# Screens.net
KiCad netlist of a schematic drawn in Altium Designer
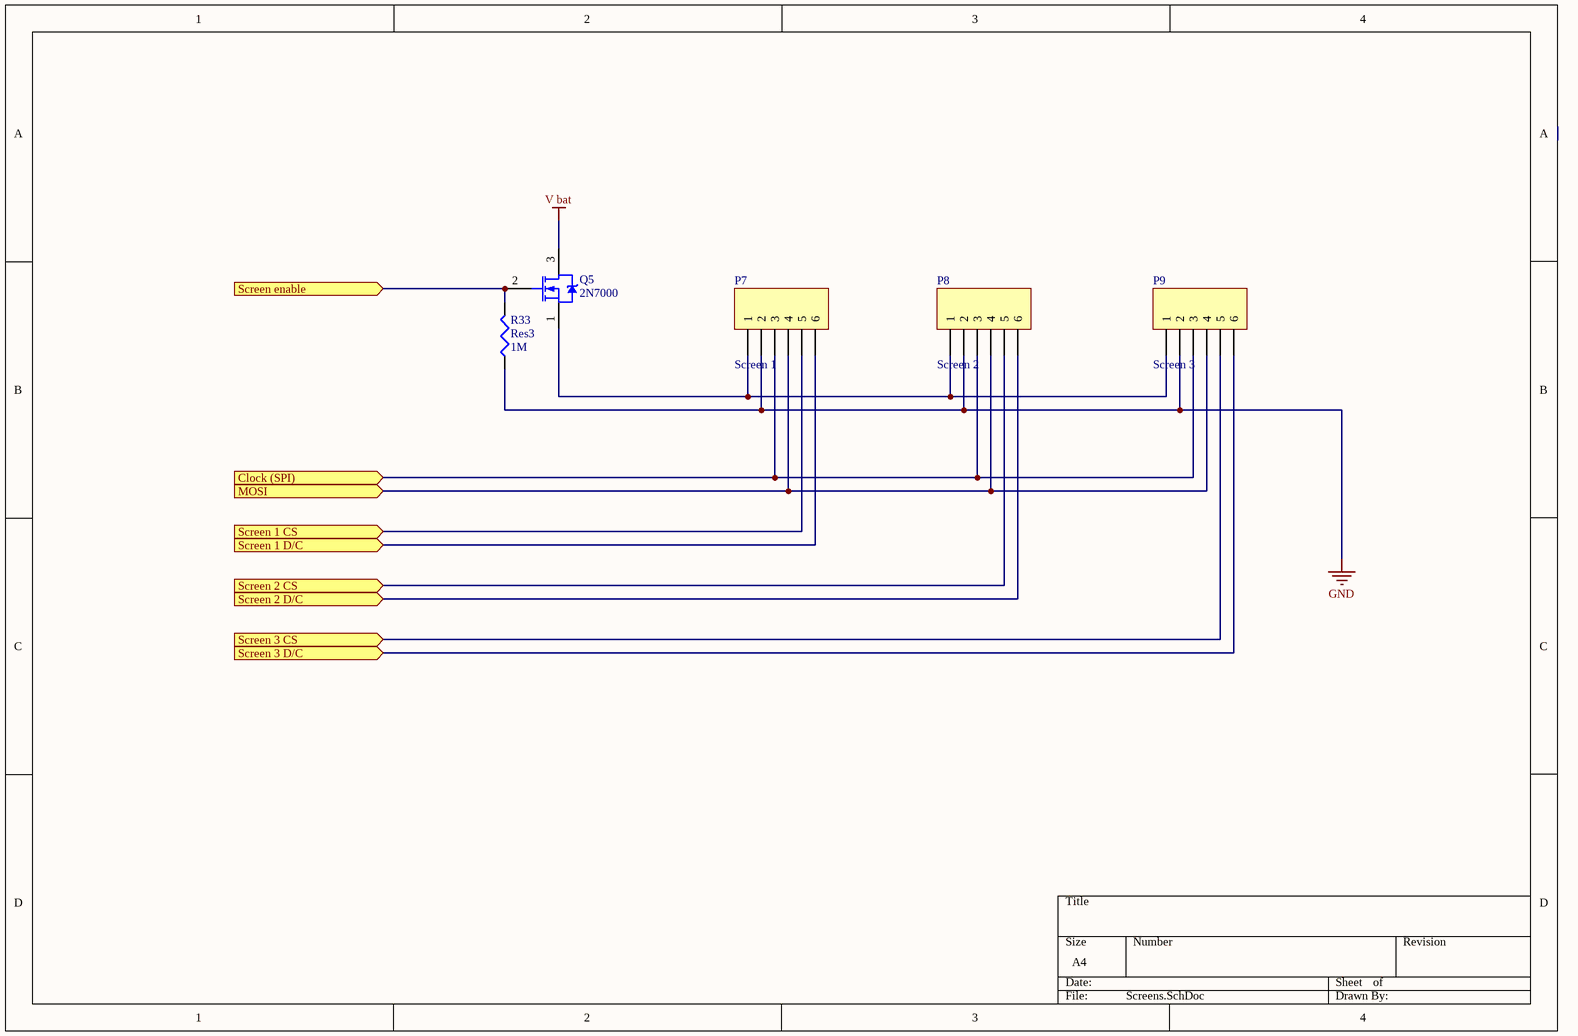
[diagram p0: Screens.SchDoc]

(export (version "E")
  (design (tool "Eeschema 10.0.6"))
  (components
    (comp (ref "P7")
      (value "Screen 1")
      (footprint "HDR1X6")
      (description "Header, 6-Pin")
      (fields (field (name "PUBLISHER") "Altium Limited"))
      (libsource (lib "Miscellaneous Connectors") (part "Header 6"))
    )
    (comp (ref "P8")
      (value "Screen 2")
      (footprint "HDR1X6")
      (description "Header, 6-Pin")
      (fields (field (name "PUBLISHER") "Altium Limited"))
      (libsource (lib "Miscellaneous Connectors") (part "Header 6"))
    )
    (comp (ref "P9")
      (value "Screen 3")
      (footprint "HDR1X6")
      (description "Header, 6-Pin")
      (fields (field (name "PUBLISHER") "Altium Limited"))
      (libsource (lib "Miscellaneous Connectors") (part "Header 6"))
    )
    (comp (ref "Q5")
      (value "2N7000")
      (footprint "ONSC-SOT-323-3-419-04_V")
      (description "Small Signal MOSFET, 200 mA, 60 V, N-Channel, 3-Pin TO-92, Bulk Box")
      (fields (field (name "MANUFACTURER") "On Semiconductor"))
      (libsource (lib "ON Semi MOSFETs") (part "2N7000"))
    )
    (comp (ref "R33")
      (value "Res3")
      (footprint "0402")
      (description "Resistor")
      (fields (field (name "ALTIUM_VALUE") "1M") (field (name "PUBLISHER") "Altium Limited"))
      (libsource (lib "Miscellaneous Devices") (part "Res3"))
    )
  )
  (nets
    (net (code "1") (name "/Clock (SPI)") (class "Default")
      (node (ref "P7") (pin "3") (pinfunction "3_3") (pintype "passive"))
      (node (ref "P8") (pin "3") (pinfunction "3_3") (pintype "passive"))
      (node (ref "P9") (pin "3") (pinfunction "3_3") (pintype "passive"))
    )
    (net (code "2") (name "/MOSI") (class "Default")
      (node (ref "P7") (pin "4") (pinfunction "4_4") (pintype "passive"))
      (node (ref "P8") (pin "4") (pinfunction "4_4") (pintype "passive"))
      (node (ref "P9") (pin "4") (pinfunction "4_4") (pintype "passive"))
    )
    (net (code "3") (name "/Screen 1 CS") (class "Default")
      (node (ref "P7") (pin "5") (pinfunction "5_5") (pintype "passive"))
    )
    (net (code "4") (name "/Screen 1 D{slash}C") (class "Default")
      (node (ref "P7") (pin "6") (pinfunction "6_6") (pintype "passive"))
    )
    (net (code "5") (name "/Screen 2 CS") (class "Default")
      (node (ref "P8") (pin "5") (pinfunction "5_5") (pintype "passive"))
    )
    (net (code "6") (name "/Screen 2 D{slash}C") (class "Default")
      (node (ref "P8") (pin "6") (pinfunction "6_6") (pintype "passive"))
    )
    (net (code "7") (name "/Screen 3 CS") (class "Default")
      (node (ref "P9") (pin "5") (pinfunction "5_5") (pintype "passive"))
    )
    (net (code "8") (name "/Screen 3 D{slash}C") (class "Default")
      (node (ref "P9") (pin "6") (pinfunction "6_6") (pintype "passive"))
    )
    (net (code "9") (name "/Screen enable") (class "Default")
      (node (ref "Q5") (pin "2") (pinfunction "G_2") (pintype "passive"))
      (node (ref "R33") (pin "2") (pinfunction "2_2") (pintype "passive"))
    )
    (net (code "10") (name "GND") (class "Default")
      (node (ref "P7") (pin "2") (pinfunction "2_2") (pintype "passive"))
      (node (ref "P8") (pin "2") (pinfunction "2_2") (pintype "passive"))
      (node (ref "P9") (pin "2") (pinfunction "2_2") (pintype "passive"))
      (node (ref "R33") (pin "1") (pinfunction "1_1") (pintype "passive"))
    )
    (net (code "11") (name "Net-(Q5-S)") (class "Default")
      (node (ref "P7") (pin "1") (pinfunction "1_1") (pintype "passive"))
      (node (ref "P8") (pin "1") (pinfunction "1_1") (pintype "passive"))
      (node (ref "P9") (pin "1") (pinfunction "1_1") (pintype "passive"))
      (node (ref "Q5") (pin "1") (pinfunction "S_1") (pintype "passive"))
    )
    (net (code "12") (name "V bat") (class "Default")
      (node (ref "Q5") (pin "3") (pinfunction "D_3") (pintype "passive"))
    )
  )
)
